# 4-layer-cpwg-nomask-osh.net
KiCad netlist of a schematic drawn in EAGLE
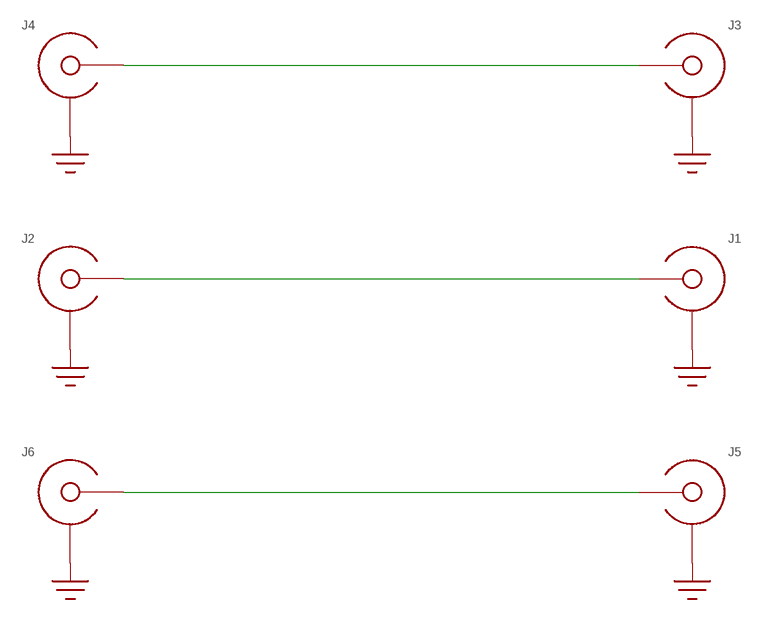
[diagram p0: schematic, sheet 1]

(export (version "E")
  (design (tool "Eeschema 10.0.6"))
  (components
    (comp (ref "J1")
      (value "SMA-EDGE-LAUNCH4L-4020-TAPER-FIXED")
      (footprint "eagle-import:SMA_EDGE_LAUNCH_4L_4020_TAPER_FIXED")
      (libsource (lib "eagle-import") (part "SMA-EDGE-LAUNCH4L-4020-TAPER-FIXED"))
    )
    (comp (ref "J2")
      (value "SMA-EDGE-LAUNCH4L-4020-TAPER-FIXED")
      (footprint "eagle-import:SMA_EDGE_LAUNCH_4L_4020_TAPER_FIXED")
      (libsource (lib "eagle-import") (part "SMA-EDGE-LAUNCH4L-4020-TAPER-FIXED"))
    )
    (comp (ref "J3")
      (value "SMA-EDGE-LAUNCH4L-4020-TAPER-FIXED")
      (footprint "eagle-import:SMA_EDGE_LAUNCH_4L_4020_TAPER_FIXED")
      (libsource (lib "eagle-import") (part "SMA-EDGE-LAUNCH4L-4020-TAPER-FIXED"))
    )
    (comp (ref "J4")
      (value "SMA-EDGE-LAUNCH4L-4020-TAPER-FIXED")
      (footprint "eagle-import:SMA_EDGE_LAUNCH_4L_4020_TAPER_FIXED")
      (libsource (lib "eagle-import") (part "SMA-EDGE-LAUNCH4L-4020-TAPER-FIXED"))
    )
    (comp (ref "J5")
      (value "SMA-EDGE-LAUNCH4L-4020-TAPER-FIXED")
      (footprint "eagle-import:SMA_EDGE_LAUNCH_4L_4020_TAPER_FIXED")
      (libsource (lib "eagle-import") (part "SMA-EDGE-LAUNCH4L-4020-TAPER-FIXED"))
    )
    (comp (ref "J6")
      (value "SMA-EDGE-LAUNCH4L-4020-TAPER-FIXED")
      (footprint "eagle-import:SMA_EDGE_LAUNCH_4L_4020_TAPER_FIXED")
      (libsource (lib "eagle-import") (part "SMA-EDGE-LAUNCH4L-4020-TAPER-FIXED"))
    )
  )
  (nets
    (net (code "1") (name "GND") (class "Default")
      (node (ref "J1") (pin "BOTTOM_GND") (pinfunction "SHIELD_BOTTOM_GND") (pintype "bidirectional"))
      (node (ref "J1") (pin "GND@1") (pinfunction "SHIELD_GND@1") (pintype "bidirectional"))
      (node (ref "J1") (pin "GND@14") (pinfunction "SHIELD_GND@14") (pintype "bidirectional"))
      (node (ref "J1") (pin "GND@15") (pinfunction "SHIELD_GND@15") (pintype "bidirectional"))
      (node (ref "J1") (pin "GND@16") (pinfunction "SHIELD_GND@16") (pintype "bidirectional"))
      (node (ref "J1") (pin "GND@17") (pinfunction "SHIELD_GND@17") (pintype "bidirectional"))
      (node (ref "J1") (pin "GND@2") (pinfunction "SHIELD_GND@2") (pintype "bidirectional"))
      (node (ref "J1") (pin "GND@3") (pinfunction "SHIELD_GND@3") (pintype "bidirectional"))
      (node (ref "J1") (pin "GND@4") (pinfunction "SHIELD_GND@4") (pintype "bidirectional"))
      (node (ref "J1") (pin "GND@5") (pinfunction "SHIELD_GND@5") (pintype "bidirectional"))
      (node (ref "J1") (pin "GND@6") (pinfunction "SHIELD_GND@6") (pintype "bidirectional"))
      (node (ref "J1") (pin "GND@7") (pinfunction "SHIELD_GND@7") (pintype "bidirectional"))
      (node (ref "J1") (pin "GND@8") (pinfunction "SHIELD_GND@8") (pintype "bidirectional"))
      (node (ref "J1") (pin "GND_PAD1") (pinfunction "SHIELD_GND_PAD1") (pintype "bidirectional"))
      (node (ref "J1") (pin "GND_PAD2") (pinfunction "SHIELD_GND_PAD2") (pintype "bidirectional"))
      (node (ref "J1") (pin "P$1") (pinfunction "SHIELD_P$1") (pintype "bidirectional"))
      (node (ref "J1") (pin "P$2") (pinfunction "SHIELD_P$2") (pintype "bidirectional"))
      (node (ref "J2") (pin "BOTTOM_GND") (pinfunction "SHIELD_BOTTOM_GND") (pintype "bidirectional"))
      (node (ref "J2") (pin "GND@1") (pinfunction "SHIELD_GND@1") (pintype "bidirectional"))
      (node (ref "J2") (pin "GND@14") (pinfunction "SHIELD_GND@14") (pintype "bidirectional"))
      (node (ref "J2") (pin "GND@15") (pinfunction "SHIELD_GND@15") (pintype "bidirectional"))
      (node (ref "J2") (pin "GND@16") (pinfunction "SHIELD_GND@16") (pintype "bidirectional"))
      (node (ref "J2") (pin "GND@17") (pinfunction "SHIELD_GND@17") (pintype "bidirectional"))
      (node (ref "J2") (pin "GND@2") (pinfunction "SHIELD_GND@2") (pintype "bidirectional"))
      (node (ref "J2") (pin "GND@3") (pinfunction "SHIELD_GND@3") (pintype "bidirectional"))
      (node (ref "J2") (pin "GND@4") (pinfunction "SHIELD_GND@4") (pintype "bidirectional"))
      (node (ref "J2") (pin "GND@5") (pinfunction "SHIELD_GND@5") (pintype "bidirectional"))
      (node (ref "J2") (pin "GND@6") (pinfunction "SHIELD_GND@6") (pintype "bidirectional"))
      (node (ref "J2") (pin "GND@7") (pinfunction "SHIELD_GND@7") (pintype "bidirectional"))
      (node (ref "J2") (pin "GND@8") (pinfunction "SHIELD_GND@8") (pintype "bidirectional"))
      (node (ref "J2") (pin "GND_PAD1") (pinfunction "SHIELD_GND_PAD1") (pintype "bidirectional"))
      (node (ref "J2") (pin "GND_PAD2") (pinfunction "SHIELD_GND_PAD2") (pintype "bidirectional"))
      (node (ref "J2") (pin "P$1") (pinfunction "SHIELD_P$1") (pintype "bidirectional"))
      (node (ref "J2") (pin "P$2") (pinfunction "SHIELD_P$2") (pintype "bidirectional"))
      (node (ref "J3") (pin "BOTTOM_GND") (pinfunction "SHIELD_BOTTOM_GND") (pintype "bidirectional"))
      (node (ref "J3") (pin "GND@1") (pinfunction "SHIELD_GND@1") (pintype "bidirectional"))
      (node (ref "J3") (pin "GND@14") (pinfunction "SHIELD_GND@14") (pintype "bidirectional"))
      (node (ref "J3") (pin "GND@15") (pinfunction "SHIELD_GND@15") (pintype "bidirectional"))
      (node (ref "J3") (pin "GND@16") (pinfunction "SHIELD_GND@16") (pintype "bidirectional"))
      (node (ref "J3") (pin "GND@17") (pinfunction "SHIELD_GND@17") (pintype "bidirectional"))
      (node (ref "J3") (pin "GND@2") (pinfunction "SHIELD_GND@2") (pintype "bidirectional"))
      (node (ref "J3") (pin "GND@3") (pinfunction "SHIELD_GND@3") (pintype "bidirectional"))
      (node (ref "J3") (pin "GND@4") (pinfunction "SHIELD_GND@4") (pintype "bidirectional"))
      (node (ref "J3") (pin "GND@5") (pinfunction "SHIELD_GND@5") (pintype "bidirectional"))
      (node (ref "J3") (pin "GND@6") (pinfunction "SHIELD_GND@6") (pintype "bidirectional"))
      (node (ref "J3") (pin "GND@7") (pinfunction "SHIELD_GND@7") (pintype "bidirectional"))
      (node (ref "J3") (pin "GND@8") (pinfunction "SHIELD_GND@8") (pintype "bidirectional"))
      (node (ref "J3") (pin "GND_PAD1") (pinfunction "SHIELD_GND_PAD1") (pintype "bidirectional"))
      (node (ref "J3") (pin "GND_PAD2") (pinfunction "SHIELD_GND_PAD2") (pintype "bidirectional"))
      (node (ref "J3") (pin "P$1") (pinfunction "SHIELD_P$1") (pintype "bidirectional"))
      (node (ref "J3") (pin "P$2") (pinfunction "SHIELD_P$2") (pintype "bidirectional"))
      (node (ref "J4") (pin "BOTTOM_GND") (pinfunction "SHIELD_BOTTOM_GND") (pintype "bidirectional"))
      (node (ref "J4") (pin "GND@1") (pinfunction "SHIELD_GND@1") (pintype "bidirectional"))
      (node (ref "J4") (pin "GND@14") (pinfunction "SHIELD_GND@14") (pintype "bidirectional"))
      (node (ref "J4") (pin "GND@15") (pinfunction "SHIELD_GND@15") (pintype "bidirectional"))
      (node (ref "J4") (pin "GND@16") (pinfunction "SHIELD_GND@16") (pintype "bidirectional"))
      (node (ref "J4") (pin "GND@17") (pinfunction "SHIELD_GND@17") (pintype "bidirectional"))
      (node (ref "J4") (pin "GND@2") (pinfunction "SHIELD_GND@2") (pintype "bidirectional"))
      (node (ref "J4") (pin "GND@3") (pinfunction "SHIELD_GND@3") (pintype "bidirectional"))
      (node (ref "J4") (pin "GND@4") (pinfunction "SHIELD_GND@4") (pintype "bidirectional"))
      (node (ref "J4") (pin "GND@5") (pinfunction "SHIELD_GND@5") (pintype "bidirectional"))
      (node (ref "J4") (pin "GND@6") (pinfunction "SHIELD_GND@6") (pintype "bidirectional"))
      (node (ref "J4") (pin "GND@7") (pinfunction "SHIELD_GND@7") (pintype "bidirectional"))
      (node (ref "J4") (pin "GND@8") (pinfunction "SHIELD_GND@8") (pintype "bidirectional"))
      (node (ref "J4") (pin "GND_PAD1") (pinfunction "SHIELD_GND_PAD1") (pintype "bidirectional"))
      (node (ref "J4") (pin "GND_PAD2") (pinfunction "SHIELD_GND_PAD2") (pintype "bidirectional"))
      (node (ref "J4") (pin "P$1") (pinfunction "SHIELD_P$1") (pintype "bidirectional"))
      (node (ref "J4") (pin "P$2") (pinfunction "SHIELD_P$2") (pintype "bidirectional"))
      (node (ref "J5") (pin "BOTTOM_GND") (pinfunction "SHIELD_BOTTOM_GND") (pintype "bidirectional"))
      (node (ref "J5") (pin "GND@1") (pinfunction "SHIELD_GND@1") (pintype "bidirectional"))
      (node (ref "J5") (pin "GND@14") (pinfunction "SHIELD_GND@14") (pintype "bidirectional"))
      (node (ref "J5") (pin "GND@15") (pinfunction "SHIELD_GND@15") (pintype "bidirectional"))
      (node (ref "J5") (pin "GND@16") (pinfunction "SHIELD_GND@16") (pintype "bidirectional"))
      (node (ref "J5") (pin "GND@17") (pinfunction "SHIELD_GND@17") (pintype "bidirectional"))
      (node (ref "J5") (pin "GND@2") (pinfunction "SHIELD_GND@2") (pintype "bidirectional"))
      (node (ref "J5") (pin "GND@3") (pinfunction "SHIELD_GND@3") (pintype "bidirectional"))
      (node (ref "J5") (pin "GND@4") (pinfunction "SHIELD_GND@4") (pintype "bidirectional"))
      (node (ref "J5") (pin "GND@5") (pinfunction "SHIELD_GND@5") (pintype "bidirectional"))
      (node (ref "J5") (pin "GND@6") (pinfunction "SHIELD_GND@6") (pintype "bidirectional"))
      (node (ref "J5") (pin "GND@7") (pinfunction "SHIELD_GND@7") (pintype "bidirectional"))
      (node (ref "J5") (pin "GND@8") (pinfunction "SHIELD_GND@8") (pintype "bidirectional"))
      (node (ref "J5") (pin "GND_PAD1") (pinfunction "SHIELD_GND_PAD1") (pintype "bidirectional"))
      (node (ref "J5") (pin "GND_PAD2") (pinfunction "SHIELD_GND_PAD2") (pintype "bidirectional"))
      (node (ref "J5") (pin "P$1") (pinfunction "SHIELD_P$1") (pintype "bidirectional"))
      (node (ref "J5") (pin "P$2") (pinfunction "SHIELD_P$2") (pintype "bidirectional"))
      (node (ref "J6") (pin "BOTTOM_GND") (pinfunction "SHIELD_BOTTOM_GND") (pintype "bidirectional"))
      (node (ref "J6") (pin "GND@1") (pinfunction "SHIELD_GND@1") (pintype "bidirectional"))
      (node (ref "J6") (pin "GND@14") (pinfunction "SHIELD_GND@14") (pintype "bidirectional"))
      (node (ref "J6") (pin "GND@15") (pinfunction "SHIELD_GND@15") (pintype "bidirectional"))
      (node (ref "J6") (pin "GND@16") (pinfunction "SHIELD_GND@16") (pintype "bidirectional"))
      (node (ref "J6") (pin "GND@17") (pinfunction "SHIELD_GND@17") (pintype "bidirectional"))
      (node (ref "J6") (pin "GND@2") (pinfunction "SHIELD_GND@2") (pintype "bidirectional"))
      (node (ref "J6") (pin "GND@3") (pinfunction "SHIELD_GND@3") (pintype "bidirectional"))
      (node (ref "J6") (pin "GND@4") (pinfunction "SHIELD_GND@4") (pintype "bidirectional"))
      (node (ref "J6") (pin "GND@5") (pinfunction "SHIELD_GND@5") (pintype "bidirectional"))
      (node (ref "J6") (pin "GND@6") (pinfunction "SHIELD_GND@6") (pintype "bidirectional"))
      (node (ref "J6") (pin "GND@7") (pinfunction "SHIELD_GND@7") (pintype "bidirectional"))
      (node (ref "J6") (pin "GND@8") (pinfunction "SHIELD_GND@8") (pintype "bidirectional"))
      (node (ref "J6") (pin "GND_PAD1") (pinfunction "SHIELD_GND_PAD1") (pintype "bidirectional"))
      (node (ref "J6") (pin "GND_PAD2") (pinfunction "SHIELD_GND_PAD2") (pintype "bidirectional"))
      (node (ref "J6") (pin "P$1") (pinfunction "SHIELD_P$1") (pintype "bidirectional"))
      (node (ref "J6") (pin "P$2") (pinfunction "SHIELD_P$2") (pintype "bidirectional"))
    )
    (net (code "2") (name "Net-(J1-CENTER-PadCENTER@1)") (class "Default")
      (node (ref "J1") (pin "CENTER@1") (pinfunction "CENTER_CENTER@1") (pintype "bidirectional"))
      (node (ref "J1") (pin "P$3") (pinfunction "CENTER_P$3") (pintype "bidirectional"))
      (node (ref "J2") (pin "CENTER@1") (pinfunction "CENTER_CENTER@1") (pintype "bidirectional"))
      (node (ref "J2") (pin "P$3") (pinfunction "CENTER_P$3") (pintype "bidirectional"))
    )
    (net (code "3") (name "Net-(J3-CENTER-PadCENTER@1)") (class "Default")
      (node (ref "J3") (pin "CENTER@1") (pinfunction "CENTER_CENTER@1") (pintype "bidirectional"))
      (node (ref "J3") (pin "P$3") (pinfunction "CENTER_P$3") (pintype "bidirectional"))
      (node (ref "J4") (pin "CENTER@1") (pinfunction "CENTER_CENTER@1") (pintype "bidirectional"))
      (node (ref "J4") (pin "P$3") (pinfunction "CENTER_P$3") (pintype "bidirectional"))
    )
    (net (code "4") (name "Net-(J5-CENTER-PadCENTER@1)") (class "Default")
      (node (ref "J5") (pin "CENTER@1") (pinfunction "CENTER_CENTER@1") (pintype "bidirectional"))
      (node (ref "J5") (pin "P$3") (pinfunction "CENTER_P$3") (pintype "bidirectional"))
      (node (ref "J6") (pin "CENTER@1") (pinfunction "CENTER_CENTER@1") (pintype "bidirectional"))
      (node (ref "J6") (pin "P$3") (pinfunction "CENTER_P$3") (pintype "bidirectional"))
    )
  )
)
